# MSXII_Controller_Breakout.net
KiCad netlist of a schematic drawn in Altium Designer
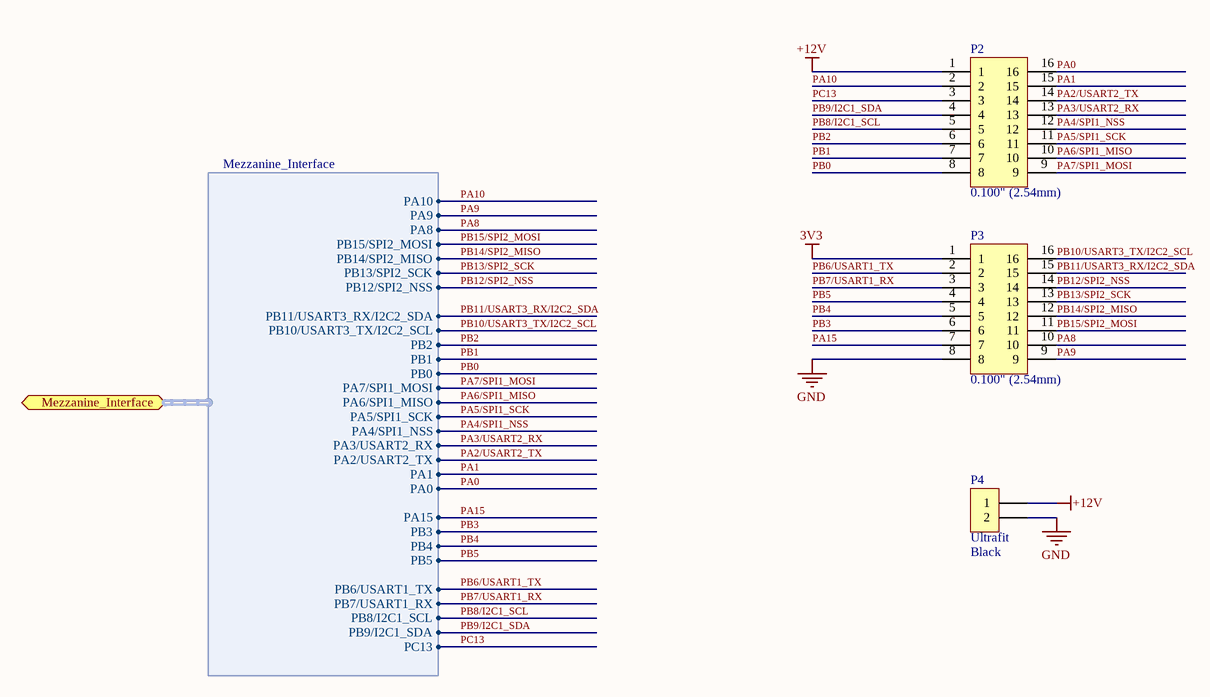
[diagram p0: MSXII_Controller_Breakout.SchDoc]

(export (version "E")
  (design (tool "Eeschema 10.0.6"))
  (components
    (comp (ref "P2")
      (value "16POS")
      (footprint "CONN, 16POS 0.100\" Header")
      (description "CONN HEADER .100\" DUAL STR 16POS")
      (fields (field (name "PITCH - MATING") "0.100\" (2.54mm)"))
      (libsource (lib "Schematic Diagrams") (part "CONN 16POS HEADR MALE 0.1{dblquote}"))
    )
    (comp (ref "P3")
      (value "16POS")
      (footprint "CONN, 16POS 0.100\" Header")
      (description "CONN HEADER .100\" DUAL STR 16POS")
      (fields (field (name "PITCH - MATING") "0.100\" (2.54mm)"))
      (libsource (lib "Schematic Diagrams") (part "CONN 16POS HEADR MALE 0.1{dblquote}"))
    )
    (comp (ref "P4")
      (value "CONN 2POS ULTRA-FIT 0.138\"")
      (footprint "CONN, 2POS ULTRA-FIT")
      (description "2 Positions Header, Shrouded Connector 0.138\" (3.50mm) Through Hole Gold")
      (fields
        (field (name "MANUFACTURER") "Molex, LLC")
        (field (name "MANUFACTURER PART NUMBER") "1722871102")
        (field (name "INSULATION COLOR") "Black")
        (field (name "SERIES") "Ultrafit")
      )
      (libsource (lib "Schematic Diagrams") (part "CONN 2POS ULTRA-FIT 0.138{dblquote}"))
    )
  )
  (nets
    (net (code "2") (name "+12V") (class "Default")
      (node (ref "P2") (pin "1") (pinfunction "1_1") (pintype "passive"))
      (node (ref "P4") (pin "1") (pinfunction "1_1") (pintype "passive"))
    )
    (net (code "3") (name "/PA0") (class "Default")
      (node (ref "P2") (pin "16") (pinfunction "16_16") (pintype "passive"))
    )
    (net (code "4") (name "/PA1") (class "Default")
      (node (ref "P2") (pin "15") (pinfunction "15_15") (pintype "passive"))
    )
    (net (code "5") (name "/PA2{slash}USART2_TX") (class "Default")
      (node (ref "P2") (pin "14") (pinfunction "14_14") (pintype "passive"))
    )
    (net (code "6") (name "/PA3{slash}USART2_RX") (class "Default")
      (node (ref "P2") (pin "13") (pinfunction "13_13") (pintype "passive"))
    )
    (net (code "7") (name "/PA4{slash}SPI1_NSS") (class "Default")
      (node (ref "P2") (pin "12") (pinfunction "12_12") (pintype "passive"))
    )
    (net (code "8") (name "/PA5{slash}SPI1_SCK") (class "Default")
      (node (ref "P2") (pin "11") (pinfunction "11_11") (pintype "passive"))
    )
    (net (code "9") (name "/PA6{slash}SPI1_MISO") (class "Default")
      (node (ref "P2") (pin "10") (pinfunction "10_10") (pintype "passive"))
    )
    (net (code "10") (name "/PA7{slash}SPI1_MOSI") (class "Default")
      (node (ref "P2") (pin "9") (pinfunction "9_9") (pintype "passive"))
    )
    (net (code "11") (name "/PA8") (class "Default")
      (node (ref "P3") (pin "10") (pinfunction "10_10") (pintype "passive"))
    )
    (net (code "12") (name "/PA9") (class "Default")
      (node (ref "P3") (pin "9") (pinfunction "9_9") (pintype "passive"))
    )
    (net (code "13") (name "/PA10") (class "Default")
      (node (ref "P2") (pin "2") (pinfunction "2_2") (pintype "passive"))
    )
    (net (code "14") (name "/PA15") (class "Default")
      (node (ref "P3") (pin "7") (pinfunction "7_7") (pintype "passive"))
    )
    (net (code "15") (name "/PB0") (class "Default")
      (node (ref "P2") (pin "8") (pinfunction "8_8") (pintype "passive"))
    )
    (net (code "16") (name "/PB1") (class "Default")
      (node (ref "P2") (pin "7") (pinfunction "7_7") (pintype "passive"))
    )
    (net (code "17") (name "/PB2") (class "Default")
      (node (ref "P2") (pin "6") (pinfunction "6_6") (pintype "passive"))
    )
    (net (code "18") (name "/PB3") (class "Default")
      (node (ref "P3") (pin "6") (pinfunction "6_6") (pintype "passive"))
    )
    (net (code "19") (name "/PB4") (class "Default")
      (node (ref "P3") (pin "5") (pinfunction "5_5") (pintype "passive"))
    )
    (net (code "20") (name "/PB5") (class "Default")
      (node (ref "P3") (pin "4") (pinfunction "4_4") (pintype "passive"))
    )
    (net (code "21") (name "/PB6{slash}USART1_TX") (class "Default")
      (node (ref "P3") (pin "2") (pinfunction "2_2") (pintype "passive"))
    )
    (net (code "22") (name "/PB7{slash}USART1_RX") (class "Default")
      (node (ref "P3") (pin "3") (pinfunction "3_3") (pintype "passive"))
    )
    (net (code "23") (name "/PB8{slash}I2C1_SCL") (class "Default")
      (node (ref "P2") (pin "5") (pinfunction "5_5") (pintype "passive"))
    )
    (net (code "24") (name "/PB9{slash}I2C1_SDA") (class "Default")
      (node (ref "P2") (pin "4") (pinfunction "4_4") (pintype "passive"))
    )
    (net (code "25") (name "/PB10{slash}USART3_TX{slash}I2C2_SCL") (class "Default")
      (node (ref "P3") (pin "16") (pinfunction "16_16") (pintype "passive"))
    )
    (net (code "26") (name "/PB11{slash}USART3_RX{slash}I2C2_SDA") (class "Default")
      (node (ref "P3") (pin "15") (pinfunction "15_15") (pintype "passive"))
    )
    (net (code "27") (name "/PB12{slash}SPI2_NSS") (class "Default")
      (node (ref "P3") (pin "14") (pinfunction "14_14") (pintype "passive"))
    )
    (net (code "28") (name "/PB13{slash}SPI2_SCK") (class "Default")
      (node (ref "P3") (pin "13") (pinfunction "13_13") (pintype "passive"))
    )
    (net (code "29") (name "/PB14{slash}SPI2_MISO") (class "Default")
      (node (ref "P3") (pin "12") (pinfunction "12_12") (pintype "passive"))
    )
    (net (code "30") (name "/PB15{slash}SPI2_MOSI") (class "Default")
      (node (ref "P3") (pin "11") (pinfunction "11_11") (pintype "passive"))
    )
    (net (code "31") (name "/PC13") (class "Default")
      (node (ref "P2") (pin "3") (pinfunction "3_3") (pintype "passive"))
    )
    (net (code "33") (name "3V3") (class "Default")
      (node (ref "P3") (pin "1") (pinfunction "1_1") (pintype "passive"))
    )
    (net (code "34") (name "GND") (class "Default")
      (node (ref "P3") (pin "8") (pinfunction "8_8") (pintype "passive"))
      (node (ref "P4") (pin "2") (pinfunction "2_2") (pintype "passive"))
    )
  )
)
